# M2.net
KiCad netlist of a schematic drawn in EAGLE
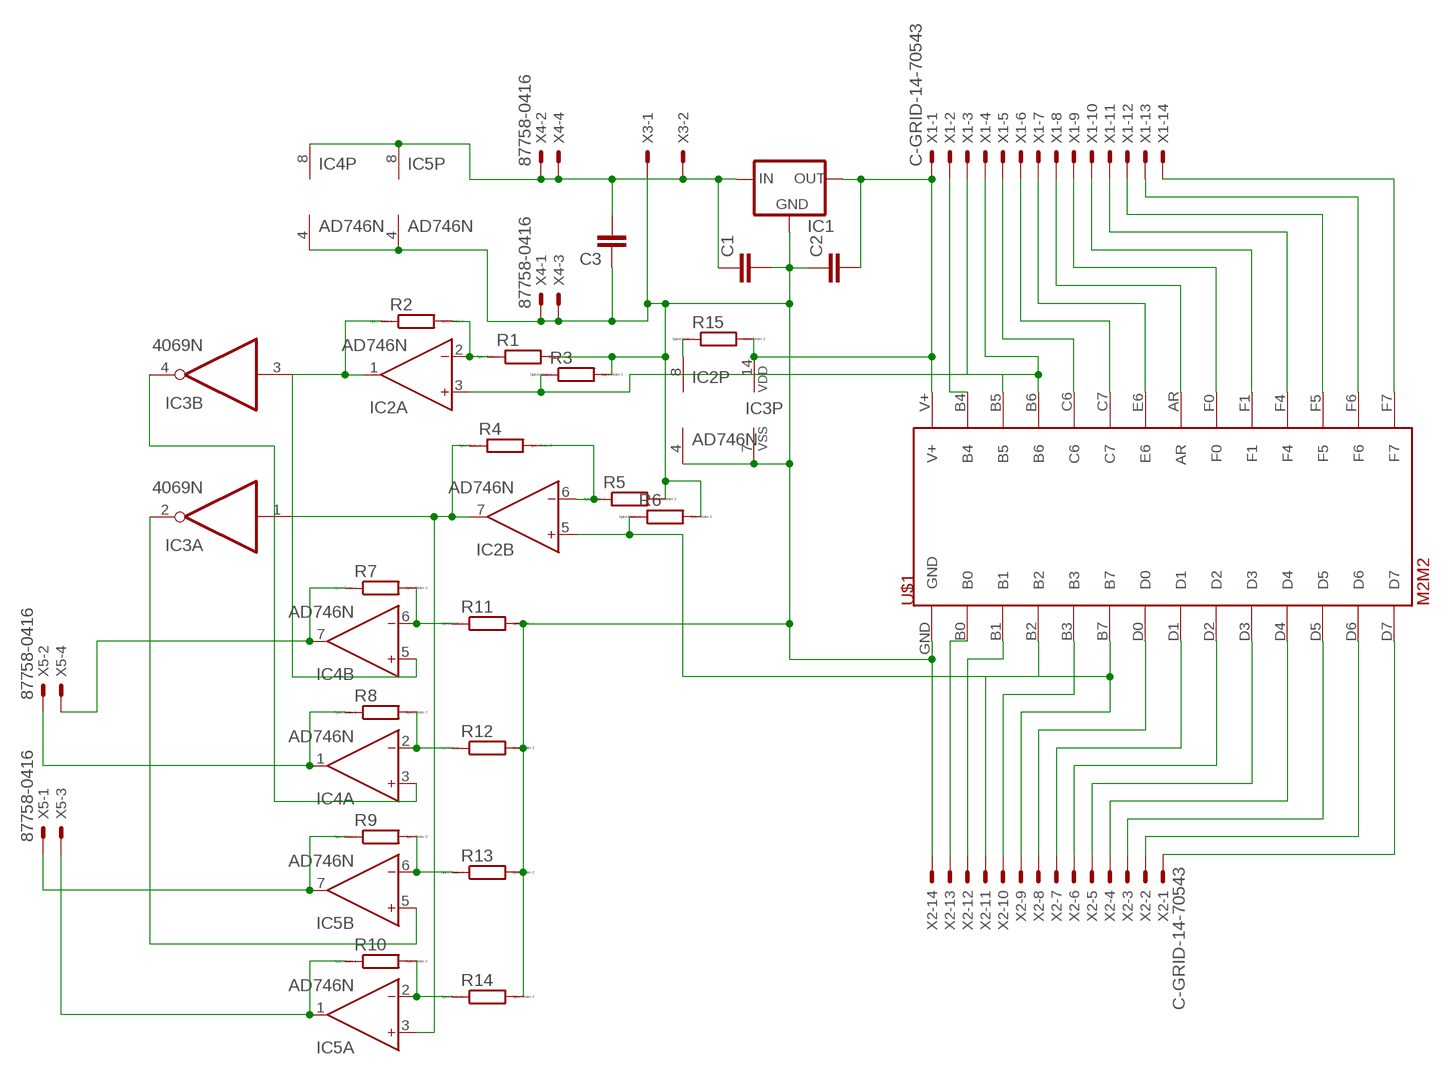
[diagram p0: schematic, sheet 1]

(export (version "E")
  (design (tool "Eeschema 10.0.6"))
  (components
    (comp (ref "C1")
      (value "C2,5-3")
      (footprint "eagle-import:C2.5-3")
      (libsource (lib "eagle-import") (part "C2,5-3"))
    )
    (comp (ref "C2")
      (value "C2,5-3")
      (footprint "eagle-import:C2.5-3")
      (libsource (lib "eagle-import") (part "C2,5-3"))
    )
    (comp (ref "C3")
      (value "C2,5-3")
      (footprint "eagle-import:C2.5-3")
      (libsource (lib "eagle-import") (part "C2,5-3"))
    )
    (comp (ref "IC1")
      (value "78MXXS")
      (footprint "eagle-import:78MXXS")
      (libsource (lib "eagle-import") (part "78MXXS"))
    )
    (comp (ref "IC2")
      (value "AD746N")
      (footprint "eagle-import:DIL08")
      (fields (field (name "MF") "ALTERA CORPORATION") (field (name "MPN") "AD746JNZ"))
      (libsource (lib "eagle-import") (part "AD746N"))
    )
    (comp (ref "IC3")
      (value "4069N")
      (footprint "eagle-import:DIL14")
      (libsource (lib "eagle-import") (part "4069N"))
    )
    (comp (ref "IC4")
      (value "AD746N")
      (footprint "eagle-import:DIL08")
      (fields (field (name "MF") "ALTERA CORPORATION") (field (name "MPN") "AD746JNZ"))
      (libsource (lib "eagle-import") (part "AD746N"))
    )
    (comp (ref "IC5")
      (value "AD746N")
      (footprint "eagle-import:DIL08")
      (fields (field (name "MF") "ALTERA CORPORATION") (field (name "MPN") "AD746JNZ"))
      (libsource (lib "eagle-import") (part "AD746N"))
    )
    (comp (ref "R1")
      (value "R0204/7")
      (footprint "eagle-import:0204_7")
      (libsource (lib "eagle-import") (part "R0204/7"))
    )
    (comp (ref "R2")
      (value "R0204/7")
      (footprint "eagle-import:0204_7")
      (libsource (lib "eagle-import") (part "R0204/7"))
    )
    (comp (ref "R3")
      (value "R0204/7")
      (footprint "eagle-import:0204_7")
      (libsource (lib "eagle-import") (part "R0204/7"))
    )
    (comp (ref "R4")
      (value "R0204/7")
      (footprint "eagle-import:0204_7")
      (libsource (lib "eagle-import") (part "R0204/7"))
    )
    (comp (ref "R5")
      (value "R0204/7")
      (footprint "eagle-import:0204_7")
      (libsource (lib "eagle-import") (part "R0204/7"))
    )
    (comp (ref "R6")
      (value "R0204/7")
      (footprint "eagle-import:0204_7")
      (libsource (lib "eagle-import") (part "R0204/7"))
    )
    (comp (ref "R7")
      (value "R0204/7")
      (footprint "eagle-import:0204_7")
      (libsource (lib "eagle-import") (part "R0204/7"))
    )
    (comp (ref "R8")
      (value "R0204/7")
      (footprint "eagle-import:0204_7")
      (libsource (lib "eagle-import") (part "R0204/7"))
    )
    (comp (ref "R9")
      (value "R0204/7")
      (footprint "eagle-import:0204_7")
      (libsource (lib "eagle-import") (part "R0204/7"))
    )
    (comp (ref "R10")
      (value "R0204/7")
      (footprint "eagle-import:0204_7")
      (libsource (lib "eagle-import") (part "R0204/7"))
    )
    (comp (ref "R11")
      (value "R0204/7")
      (footprint "eagle-import:0204_7")
      (libsource (lib "eagle-import") (part "R0204/7"))
    )
    (comp (ref "R12")
      (value "R0204/7")
      (footprint "eagle-import:0204_7")
      (libsource (lib "eagle-import") (part "R0204/7"))
    )
    (comp (ref "R13")
      (value "R0204/7")
      (footprint "eagle-import:0204_7")
      (libsource (lib "eagle-import") (part "R0204/7"))
    )
    (comp (ref "R14")
      (value "R0204/7")
      (footprint "eagle-import:0204_7")
      (libsource (lib "eagle-import") (part "R0204/7"))
    )
    (comp (ref "R15")
      (value "R0204/7")
      (footprint "eagle-import:0204_7")
      (libsource (lib "eagle-import") (part "R0204/7"))
    )
    (comp (ref "U$1")
      (value "M2M2")
      (footprint "eagle-import:M2")
      (libsource (lib "eagle-import") (part "M2M2"))
    )
    (comp (ref "X1")
      (value "C-GRID-14-70543")
      (footprint "eagle-import:70543-14")
      (libsource (lib "eagle-import") (part "C-GRID-14-70543"))
    )
    (comp (ref "X2")
      (value "C-GRID-14-70543")
      (footprint "eagle-import:70543-14")
      (libsource (lib "eagle-import") (part "C-GRID-14-70543"))
    )
    (comp (ref "X3")
      (value "KK-156-2")
      (footprint "eagle-import:KK-156-2")
      (libsource (lib "eagle-import") (part "KK-156-2"))
    )
    (comp (ref "X4")
      (value "87758-0416")
      (footprint "eagle-import:87758-0416")
      (fields (field (name "MF") "FARNELL"))
      (libsource (lib "eagle-import") (part "87758-0416"))
    )
    (comp (ref "X5")
      (value "87758-0416")
      (footprint "eagle-import:87758-0416")
      (fields (field (name "MF") "FARNELL"))
      (libsource (lib "eagle-import") (part "87758-0416"))
    )
  )
  (nets
    (net (code "1") (name "Net-(IC2A-IN+)") (class "Default")
      (node (ref "IC2") (pin "3") (pinfunction "IN+_3") (pintype "input"))
      (node (ref "R3") (pin "1") (pinfunction "1_1") (pintype "passive"))
      (node (ref "U$1") (pin "B6") (pinfunction "B6_B6") (pintype "bidirectional"))
      (node (ref "X1") (pin "4") (pinfunction "S_4") (pintype "passive"))
    )
    (net (code "2") (name "Net-(IC2A-IN-)") (class "Default")
      (node (ref "IC2") (pin "2") (pinfunction "IN-_2") (pintype "input"))
      (node (ref "R1") (pin "1") (pinfunction "1_1") (pintype "passive"))
      (node (ref "R2") (pin "2") (pinfunction "2_2") (pintype "passive"))
    )
    (net (code "3") (name "Net-(IC2A-OUT)") (class "Default")
      (node (ref "IC2") (pin "1") (pinfunction "OUT_1") (pintype "output"))
      (node (ref "IC3") (pin "3") (pinfunction "I_3") (pintype "input"))
      (node (ref "IC4") (pin "5") (pinfunction "IN+_5") (pintype "input"))
      (node (ref "R2") (pin "1") (pinfunction "1_1") (pintype "passive"))
    )
    (net (code "4") (name "Net-(IC2B-IN+)") (class "Default")
      (node (ref "IC2") (pin "5") (pinfunction "IN+_5") (pintype "input"))
      (node (ref "R6") (pin "1") (pinfunction "1_1") (pintype "passive"))
      (node (ref "U$1") (pin "B7") (pinfunction "B7_B7") (pintype "bidirectional"))
      (node (ref "X2") (pin "9") (pinfunction "S_9") (pintype "passive"))
    )
    (net (code "5") (name "Net-(IC2B-IN-)") (class "Default")
      (node (ref "IC2") (pin "6") (pinfunction "IN-_6") (pintype "input"))
      (node (ref "R4") (pin "2") (pinfunction "2_2") (pintype "passive"))
      (node (ref "R5") (pin "1") (pinfunction "1_1") (pintype "passive"))
    )
    (net (code "6") (name "Net-(IC2B-OUT)") (class "Default")
      (node (ref "IC2") (pin "7") (pinfunction "OUT_7") (pintype "output"))
      (node (ref "IC3") (pin "1") (pinfunction "I_1") (pintype "input"))
      (node (ref "IC5") (pin "3") (pinfunction "IN+_3") (pintype "input"))
      (node (ref "R4") (pin "1") (pinfunction "1_1") (pintype "passive"))
    )
    (net (code "7") (name "Net-(IC2C-V+)") (class "Default")
      (node (ref "IC2") (pin "8") (pinfunction "V+_8") (pintype "power_in"))
      (node (ref "R15") (pin "1") (pinfunction "1_1") (pintype "passive"))
    )
    (net (code "8") (name "Net-(IC2C-V-)") (class "Default")
      (node (ref "C1") (pin "2") (pinfunction "2_2") (pintype "passive"))
      (node (ref "C2") (pin "1") (pinfunction "1_1") (pintype "passive"))
      (node (ref "C3") (pin "1") (pinfunction "1_1") (pintype "passive"))
      (node (ref "IC1") (pin "GND") (pinfunction "GND_GND") (pintype "input"))
      (node (ref "IC2") (pin "4") (pinfunction "V-_4") (pintype "power_in"))
      (node (ref "IC3") (pin "7") (pinfunction "VSS_7") (pintype "power_in"))
      (node (ref "IC4") (pin "4") (pinfunction "V-_4") (pintype "power_in"))
      (node (ref "IC5") (pin "4") (pinfunction "V-_4") (pintype "power_in"))
      (node (ref "R1") (pin "2") (pinfunction "2_2") (pintype "passive"))
      (node (ref "R11") (pin "2") (pinfunction "2_2") (pintype "passive"))
      (node (ref "R12") (pin "2") (pinfunction "2_2") (pintype "passive"))
      (node (ref "R13") (pin "2") (pinfunction "2_2") (pintype "passive"))
      (node (ref "R14") (pin "2") (pinfunction "2_2") (pintype "passive"))
      (node (ref "R3") (pin "2") (pinfunction "2_2") (pintype "passive"))
      (node (ref "R5") (pin "2") (pinfunction "2_2") (pintype "passive"))
      (node (ref "R6") (pin "2") (pinfunction "2_2") (pintype "passive"))
      (node (ref "U$1") (pin "GND") (pinfunction "GND_GND") (pintype "bidirectional"))
      (node (ref "X2") (pin "14") (pinfunction "S_14") (pintype "passive"))
      (node (ref "X3") (pin "1") (pinfunction "S_1") (pintype "passive"))
      (node (ref "X4") (pin "1") (pinfunction "S_1") (pintype "passive"))
      (node (ref "X4") (pin "3") (pinfunction "S_3") (pintype "passive"))
    )
    (net (code "9") (name "Net-(IC3A-O)") (class "Default")
      (node (ref "IC3") (pin "2") (pinfunction "O_2") (pintype "output"))
      (node (ref "IC5") (pin "5") (pinfunction "IN+_5") (pintype "input"))
    )
    (net (code "10") (name "Net-(IC3B-O)") (class "Default")
      (node (ref "IC3") (pin "4") (pinfunction "O_4") (pintype "output"))
      (node (ref "IC4") (pin "3") (pinfunction "IN+_3") (pintype "input"))
    )
    (net (code "11") (name "Net-(IC3G-VDD)") (class "Default")
      (node (ref "C2") (pin "2") (pinfunction "2_2") (pintype "passive"))
      (node (ref "IC1") (pin "OUT") (pinfunction "OUT_OUT") (pintype "passive"))
      (node (ref "IC3") (pin "14") (pinfunction "VDD_14") (pintype "power_in"))
      (node (ref "R15") (pin "2") (pinfunction "2_2") (pintype "passive"))
      (node (ref "U$1") (pin "V+") (pinfunction "V+_V+") (pintype "bidirectional"))
      (node (ref "X1") (pin "1") (pinfunction "S_1") (pintype "passive"))
    )
    (net (code "12") (name "Net-(IC4A-IN-)") (class "Default")
      (node (ref "IC4") (pin "2") (pinfunction "IN-_2") (pintype "input"))
      (node (ref "R12") (pin "1") (pinfunction "1_1") (pintype "passive"))
      (node (ref "R8") (pin "2") (pinfunction "2_2") (pintype "passive"))
    )
    (net (code "13") (name "Net-(IC4A-OUT)") (class "Default")
      (node (ref "IC4") (pin "1") (pinfunction "OUT_1") (pintype "output"))
      (node (ref "R8") (pin "1") (pinfunction "1_1") (pintype "passive"))
      (node (ref "X5") (pin "2") (pinfunction "S_2") (pintype "passive"))
    )
    (net (code "14") (name "Net-(IC4B-IN-)") (class "Default")
      (node (ref "IC4") (pin "6") (pinfunction "IN-_6") (pintype "input"))
      (node (ref "R11") (pin "1") (pinfunction "1_1") (pintype "passive"))
      (node (ref "R7") (pin "2") (pinfunction "2_2") (pintype "passive"))
    )
    (net (code "15") (name "Net-(IC4B-OUT)") (class "Default")
      (node (ref "IC4") (pin "7") (pinfunction "OUT_7") (pintype "output"))
      (node (ref "R7") (pin "1") (pinfunction "1_1") (pintype "passive"))
      (node (ref "X5") (pin "4") (pinfunction "S_4") (pintype "passive"))
    )
    (net (code "16") (name "Net-(IC4C-V+)") (class "Default")
      (node (ref "C1") (pin "1") (pinfunction "1_1") (pintype "passive"))
      (node (ref "C3") (pin "2") (pinfunction "2_2") (pintype "passive"))
      (node (ref "IC1") (pin "IN") (pinfunction "IN_IN") (pintype "input"))
      (node (ref "IC4") (pin "8") (pinfunction "V+_8") (pintype "power_in"))
      (node (ref "IC5") (pin "8") (pinfunction "V+_8") (pintype "power_in"))
      (node (ref "X3") (pin "2") (pinfunction "S_2") (pintype "passive"))
      (node (ref "X4") (pin "2") (pinfunction "S_2") (pintype "passive"))
      (node (ref "X4") (pin "4") (pinfunction "S_4") (pintype "passive"))
    )
    (net (code "17") (name "Net-(IC5A-IN-)") (class "Default")
      (node (ref "IC5") (pin "2") (pinfunction "IN-_2") (pintype "input"))
      (node (ref "R10") (pin "2") (pinfunction "2_2") (pintype "passive"))
      (node (ref "R14") (pin "1") (pinfunction "1_1") (pintype "passive"))
    )
    (net (code "18") (name "Net-(IC5A-OUT)") (class "Default")
      (node (ref "IC5") (pin "1") (pinfunction "OUT_1") (pintype "output"))
      (node (ref "R10") (pin "1") (pinfunction "1_1") (pintype "passive"))
      (node (ref "X5") (pin "3") (pinfunction "S_3") (pintype "passive"))
    )
    (net (code "19") (name "Net-(IC5B-IN-)") (class "Default")
      (node (ref "IC5") (pin "6") (pinfunction "IN-_6") (pintype "input"))
      (node (ref "R13") (pin "1") (pinfunction "1_1") (pintype "passive"))
      (node (ref "R9") (pin "2") (pinfunction "2_2") (pintype "passive"))
    )
    (net (code "20") (name "Net-(IC5B-OUT)") (class "Default")
      (node (ref "IC5") (pin "7") (pinfunction "OUT_7") (pintype "output"))
      (node (ref "R9") (pin "1") (pinfunction "1_1") (pintype "passive"))
      (node (ref "X5") (pin "1") (pinfunction "S_1") (pintype "passive"))
    )
    (net (code "21") (name "Net-(X1B-S)") (class "Default")
      (node (ref "U$1") (pin "F1") (pinfunction "F1_F1") (pintype "bidirectional"))
      (node (ref "X1") (pin "10") (pinfunction "S_10") (pintype "passive"))
    )
    (net (code "22") (name "Net-(X1C-S)") (class "Default")
      (node (ref "U$1") (pin "F4") (pinfunction "F4_F4") (pintype "bidirectional"))
      (node (ref "X1") (pin "11") (pinfunction "S_11") (pintype "passive"))
    )
    (net (code "23") (name "Net-(X1D-S)") (class "Default")
      (node (ref "U$1") (pin "F5") (pinfunction "F5_F5") (pintype "bidirectional"))
      (node (ref "X1") (pin "12") (pinfunction "S_12") (pintype "passive"))
    )
    (net (code "24") (name "Net-(X1E-S)") (class "Default")
      (node (ref "U$1") (pin "F6") (pinfunction "F6_F6") (pintype "bidirectional"))
      (node (ref "X1") (pin "13") (pinfunction "S_13") (pintype "passive"))
    )
    (net (code "25") (name "Net-(X1F-S)") (class "Default")
      (node (ref "U$1") (pin "F7") (pinfunction "F7_F7") (pintype "bidirectional"))
      (node (ref "X1") (pin "14") (pinfunction "S_14") (pintype "passive"))
    )
    (net (code "26") (name "Net-(X1G-S)") (class "Default")
      (node (ref "U$1") (pin "B4") (pinfunction "B4_B4") (pintype "bidirectional"))
      (node (ref "X1") (pin "2") (pinfunction "S_2") (pintype "passive"))
    )
    (net (code "27") (name "Net-(X1H-S)") (class "Default")
      (node (ref "U$1") (pin "B5") (pinfunction "B5_B5") (pintype "bidirectional"))
      (node (ref "X1") (pin "3") (pinfunction "S_3") (pintype "passive"))
    )
    (net (code "28") (name "Net-(X1J-S)") (class "Default")
      (node (ref "U$1") (pin "C6") (pinfunction "C6_C6") (pintype "bidirectional"))
      (node (ref "X1") (pin "5") (pinfunction "S_5") (pintype "passive"))
    )
    (net (code "29") (name "Net-(X1K-S)") (class "Default")
      (node (ref "U$1") (pin "C7") (pinfunction "C7_C7") (pintype "bidirectional"))
      (node (ref "X1") (pin "6") (pinfunction "S_6") (pintype "passive"))
    )
    (net (code "30") (name "Net-(X1L-S)") (class "Default")
      (node (ref "U$1") (pin "E6") (pinfunction "E6_E6") (pintype "bidirectional"))
      (node (ref "X1") (pin "7") (pinfunction "S_7") (pintype "passive"))
    )
    (net (code "31") (name "Net-(X1M-S)") (class "Default")
      (node (ref "U$1") (pin "AR") (pinfunction "AR_AR") (pintype "bidirectional"))
      (node (ref "X1") (pin "8") (pinfunction "S_8") (pintype "passive"))
    )
    (net (code "32") (name "Net-(X1N-S)") (class "Default")
      (node (ref "U$1") (pin "F0") (pinfunction "F0_F0") (pintype "bidirectional"))
      (node (ref "X1") (pin "9") (pinfunction "S_9") (pintype "passive"))
    )
    (net (code "33") (name "Net-(X2A-S)") (class "Default")
      (node (ref "U$1") (pin "D7") (pinfunction "D7_D7") (pintype "bidirectional"))
      (node (ref "X2") (pin "1") (pinfunction "S_1") (pintype "passive"))
    )
    (net (code "34") (name "Net-(X2B-S)") (class "Default")
      (node (ref "U$1") (pin "B3") (pinfunction "B3_B3") (pintype "bidirectional"))
      (node (ref "X2") (pin "10") (pinfunction "S_10") (pintype "passive"))
    )
    (net (code "35") (name "Net-(X2C-S)") (class "Default")
      (node (ref "U$1") (pin "B2") (pinfunction "B2_B2") (pintype "bidirectional"))
      (node (ref "X2") (pin "11") (pinfunction "S_11") (pintype "passive"))
    )
    (net (code "36") (name "Net-(X2D-S)") (class "Default")
      (node (ref "U$1") (pin "B1") (pinfunction "B1_B1") (pintype "bidirectional"))
      (node (ref "X2") (pin "12") (pinfunction "S_12") (pintype "passive"))
    )
    (net (code "37") (name "Net-(X2E-S)") (class "Default")
      (node (ref "U$1") (pin "B0") (pinfunction "B0_B0") (pintype "bidirectional"))
      (node (ref "X2") (pin "13") (pinfunction "S_13") (pintype "passive"))
    )
    (net (code "38") (name "Net-(X2G-S)") (class "Default")
      (node (ref "U$1") (pin "D6") (pinfunction "D6_D6") (pintype "bidirectional"))
      (node (ref "X2") (pin "2") (pinfunction "S_2") (pintype "passive"))
    )
    (net (code "39") (name "Net-(X2H-S)") (class "Default")
      (node (ref "U$1") (pin "D5") (pinfunction "D5_D5") (pintype "bidirectional"))
      (node (ref "X2") (pin "3") (pinfunction "S_3") (pintype "passive"))
    )
    (net (code "40") (name "Net-(X2I-S)") (class "Default")
      (node (ref "U$1") (pin "D4") (pinfunction "D4_D4") (pintype "bidirectional"))
      (node (ref "X2") (pin "4") (pinfunction "S_4") (pintype "passive"))
    )
    (net (code "41") (name "Net-(X2J-S)") (class "Default")
      (node (ref "U$1") (pin "D3") (pinfunction "D3_D3") (pintype "bidirectional"))
      (node (ref "X2") (pin "5") (pinfunction "S_5") (pintype "passive"))
    )
    (net (code "42") (name "Net-(X2K-S)") (class "Default")
      (node (ref "U$1") (pin "D2") (pinfunction "D2_D2") (pintype "bidirectional"))
      (node (ref "X2") (pin "6") (pinfunction "S_6") (pintype "passive"))
    )
    (net (code "43") (name "Net-(X2L-S)") (class "Default")
      (node (ref "U$1") (pin "D1") (pinfunction "D1_D1") (pintype "bidirectional"))
      (node (ref "X2") (pin "7") (pinfunction "S_7") (pintype "passive"))
    )
    (net (code "44") (name "Net-(X2M-S)") (class "Default")
      (node (ref "U$1") (pin "D0") (pinfunction "D0_D0") (pintype "bidirectional"))
      (node (ref "X2") (pin "8") (pinfunction "S_8") (pintype "passive"))
    )
  )
)
